# Diag64Cart.net
KiCad netlist of a schematic drawn in EAGLE
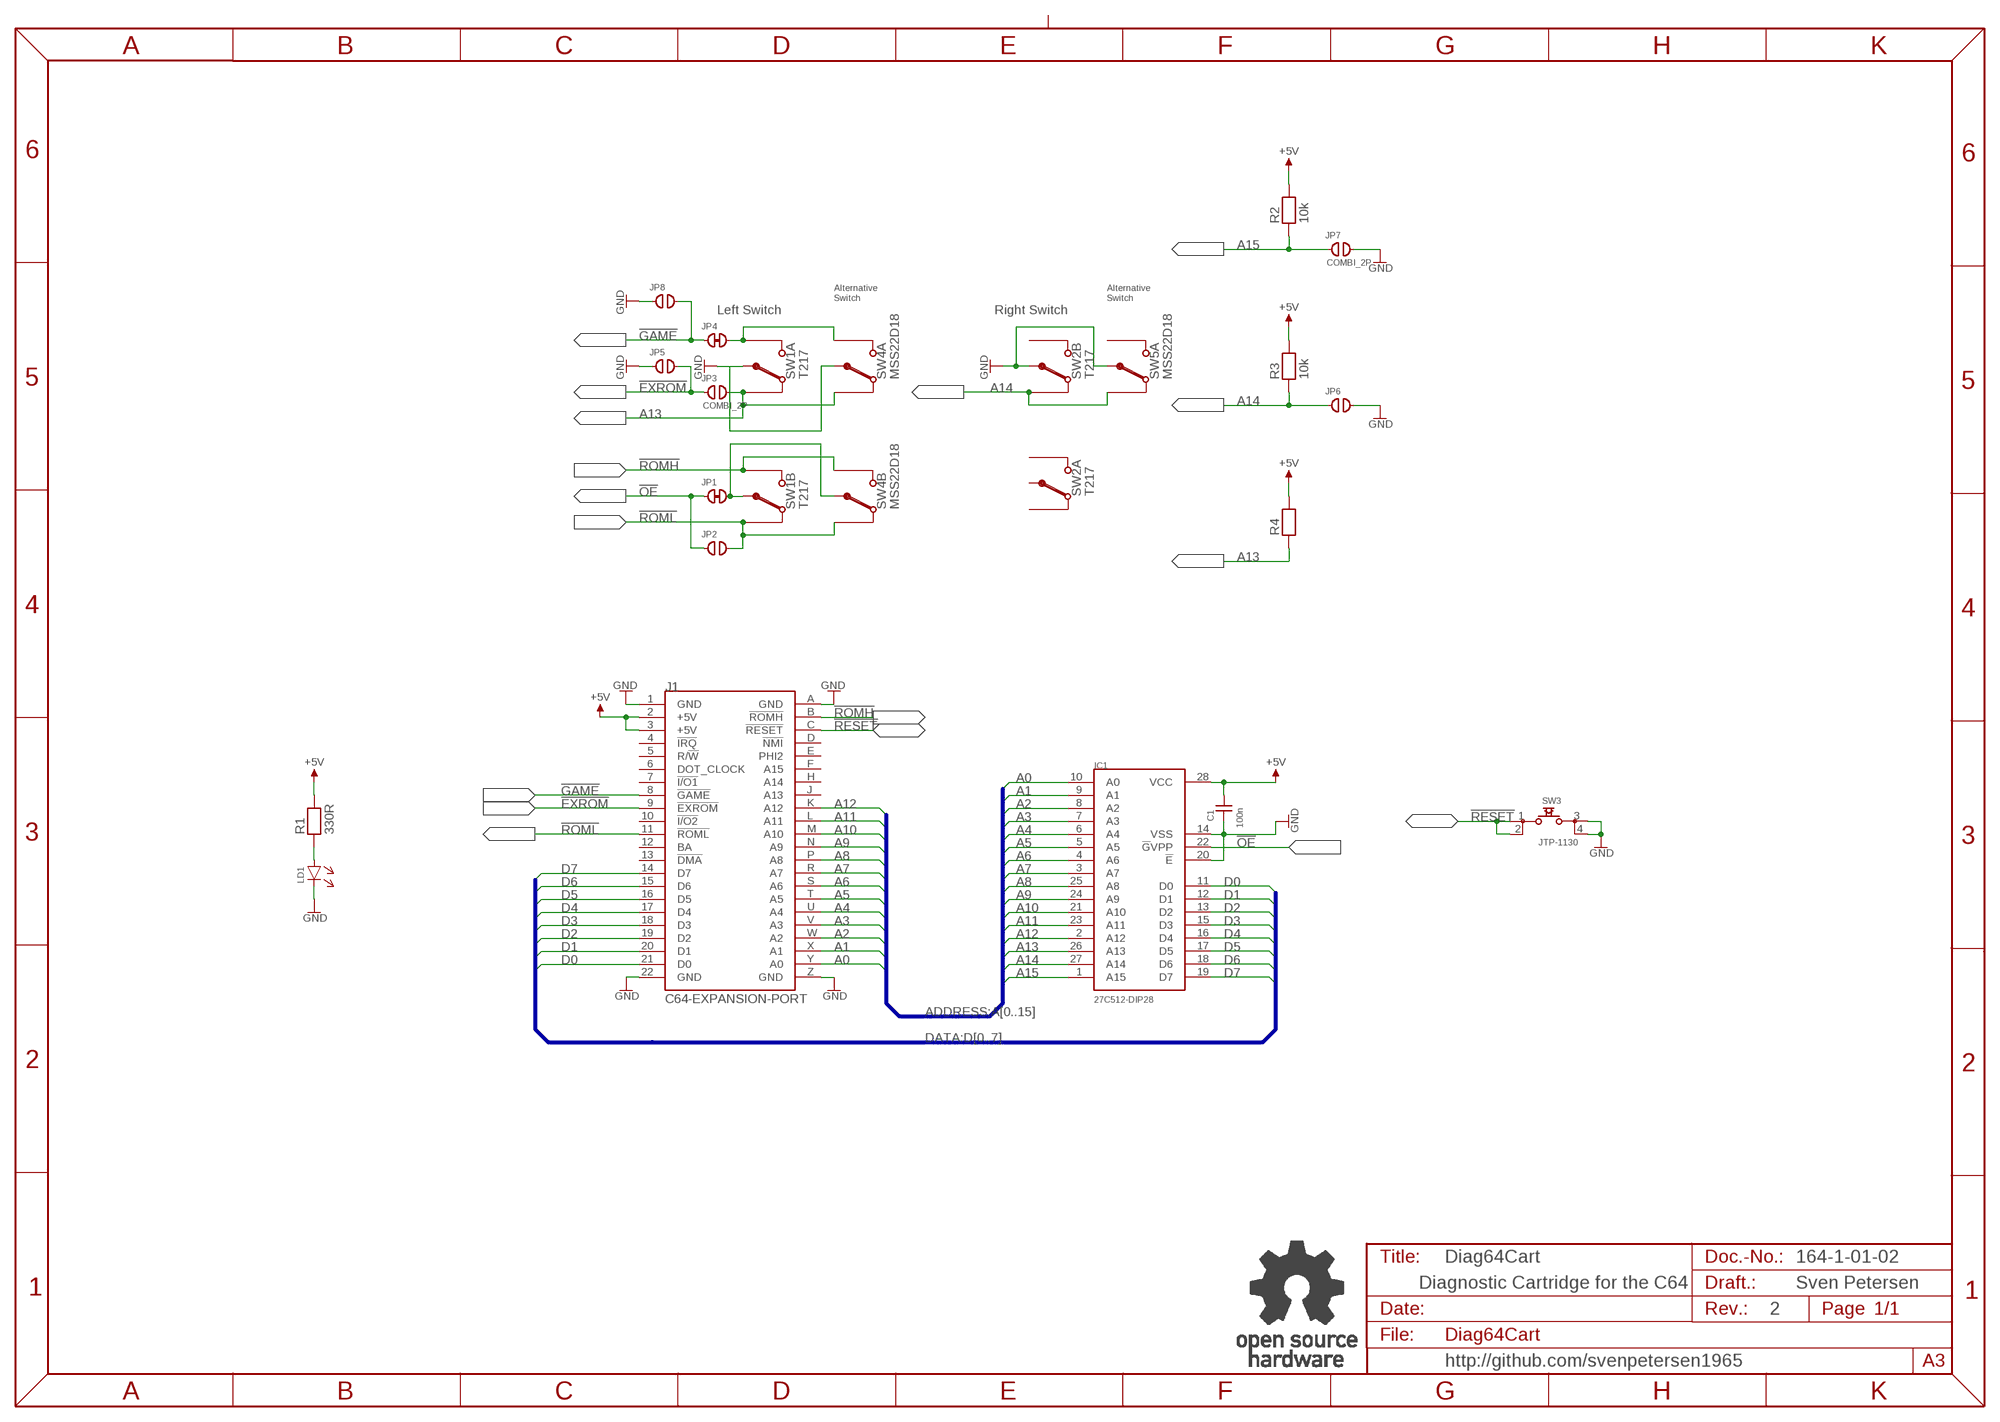
[diagram p0: schematic, sheet 1]

(export (version "E")
  (design (tool "Eeschema 10.0.6"))
  (components
    (comp (ref "C1")
      (value "100n")
      (footprint "eagle-import:C-2,5")
      (libsource (lib "eagle-import") (part "CAP01"))
    )
    (comp (ref "IC1")
      (value "27C512-DIP28")
      (footprint "eagle-import:DIL28-6")
      (libsource (lib "eagle-import") (part "M27C512-DIP28"))
    )
    (comp (ref "J1")
      (value "C64-EXPANSION-PORT")
      (footprint "eagle-import:EXPANSIO_SQ")
      (libsource (lib "eagle-import") (part "C64-EXPANSIONPNARROW"))
    )
    (comp (ref "JP1")
      (value "CLOSED")
      (footprint "eagle-import:CP_CL")
      (libsource (lib "eagle-import") (part "CLOSED"))
    )
    (comp (ref "JP2")
      (value "OPEN")
      (footprint "eagle-import:CP_OP")
      (libsource (lib "eagle-import") (part "OPEN"))
    )
    (comp (ref "JP3")
      (value "COMBI_2P")
      (footprint "eagle-import:COMBI-2P")
      (libsource (lib "eagle-import") (part "COMBI_2P"))
    )
    (comp (ref "JP4")
      (value "CLOSED")
      (footprint "eagle-import:CP_CL")
      (libsource (lib "eagle-import") (part "CLOSED"))
    )
    (comp (ref "JP5")
      (value "OPEN")
      (footprint "eagle-import:CP_OP")
      (libsource (lib "eagle-import") (part "OPEN"))
    )
    (comp (ref "JP6")
      (value "OPEN")
      (footprint "eagle-import:CP_OP")
      (libsource (lib "eagle-import") (part "OPEN"))
    )
    (comp (ref "JP7")
      (value "COMBI_2P")
      (footprint "eagle-import:COMBI-2P")
      (libsource (lib "eagle-import") (part "COMBI_2P"))
    )
    (comp (ref "JP8")
      (value "OPEN")
      (footprint "eagle-import:CP_OP")
      (libsource (lib "eagle-import") (part "OPEN"))
    )
    (comp (ref "LD1")
      (value "3MM")
      (footprint "eagle-import:3MM")
      (libsource (lib "eagle-import") (part "3MM"))
    )
    (comp (ref "R1")
      (value "330R")
      (footprint "eagle-import:R-10")
      (libsource (lib "eagle-import") (part "RES04"))
    )
    (comp (ref "R2")
      (value "10k")
      (footprint "eagle-import:R-10")
      (libsource (lib "eagle-import") (part "RES04"))
    )
    (comp (ref "R3")
      (value "10k")
      (footprint "eagle-import:R-10")
      (libsource (lib "eagle-import") (part "RES04"))
    )
    (comp (ref "R4")
      (value "10k")
      (footprint "eagle-import:R-10")
      (libsource (lib "eagle-import") (part "RES04"))
    )
    (comp (ref "SW1")
      (value "T217")
      (footprint "eagle-import:T217_SIDE")
      (libsource (lib "eagle-import") (part "T217"))
    )
    (comp (ref "SW2")
      (value "T217")
      (footprint "eagle-import:T217_SIDE")
      (libsource (lib "eagle-import") (part "T217"))
    )
    (comp (ref "SW3")
      (value "JTP-1130")
      (footprint "eagle-import:JTP-1130")
      (libsource (lib "eagle-import") (part "JTP-1130"))
    )
    (comp (ref "SW4")
      (value "MSS22D18")
      (footprint "eagle-import:DPDT_9MM")
      (libsource (lib "eagle-import") (part "DPDT_9MM"))
    )
    (comp (ref "SW5")
      (value "MSS22D18")
      (footprint "eagle-import:DPDT_9MM")
      (libsource (lib "eagle-import") (part "DPDT_9MM"))
    )
    (comp (ref "U$43")
      (value "OPEN_SOURCE_HW")
      (footprint "eagle-import:OPENHW")
      (libsource (lib "eagle-import") (part "OPEN_SOURCE_HW"))
    )
  )
  (nets
    (net (code "25") (name "+5V") (class "Default")
      (node (ref "C1") (pin "2") (pinfunction "2_2") (pintype "passive"))
      (node (ref "IC1") (pin "28") (pinfunction "VCC_28") (pintype "power_in"))
      (node (ref "J1") (pin "2") (pinfunction "+5V_2") (pintype "power_in"))
      (node (ref "J1") (pin "3") (pinfunction "+5V_3") (pintype "power_in"))
      (node (ref "R1") (pin "2") (pinfunction "2_2") (pintype "passive"))
      (node (ref "R2") (pin "2") (pinfunction "2_2") (pintype "passive"))
      (node (ref "R3") (pin "2") (pinfunction "2_2") (pintype "passive"))
      (node (ref "R4") (pin "2") (pinfunction "2_2") (pintype "passive"))
    )
    (net (code "26") (name "/A0") (class "Default")
      (node (ref "IC1") (pin "10") (pinfunction "A0_10") (pintype "input"))
      (node (ref "J1") (pin "Y") (pinfunction "A0_Y") (pintype "bidirectional"))
    )
    (net (code "27") (name "/A1") (class "Default")
      (node (ref "IC1") (pin "9") (pinfunction "A1_9") (pintype "input"))
      (node (ref "J1") (pin "X") (pinfunction "A1_X") (pintype "bidirectional"))
    )
    (net (code "28") (name "/A2") (class "Default")
      (node (ref "IC1") (pin "8") (pinfunction "A2_8") (pintype "input"))
      (node (ref "J1") (pin "W") (pinfunction "A2_W") (pintype "bidirectional"))
    )
    (net (code "29") (name "/A3") (class "Default")
      (node (ref "IC1") (pin "7") (pinfunction "A3_7") (pintype "input"))
      (node (ref "J1") (pin "V") (pinfunction "A3_V") (pintype "bidirectional"))
    )
    (net (code "30") (name "/A4") (class "Default")
      (node (ref "IC1") (pin "6") (pinfunction "A4_6") (pintype "input"))
      (node (ref "J1") (pin "U") (pinfunction "A4_U") (pintype "bidirectional"))
    )
    (net (code "31") (name "/A5") (class "Default")
      (node (ref "IC1") (pin "5") (pinfunction "A5_5") (pintype "input"))
      (node (ref "J1") (pin "T") (pinfunction "A5_T") (pintype "bidirectional"))
    )
    (net (code "32") (name "/A6") (class "Default")
      (node (ref "IC1") (pin "4") (pinfunction "A6_4") (pintype "input"))
      (node (ref "J1") (pin "S") (pinfunction "A6_S") (pintype "bidirectional"))
    )
    (net (code "33") (name "/A7") (class "Default")
      (node (ref "IC1") (pin "3") (pinfunction "A7_3") (pintype "input"))
      (node (ref "J1") (pin "R") (pinfunction "A7_R") (pintype "bidirectional"))
    )
    (net (code "34") (name "/A8") (class "Default")
      (node (ref "IC1") (pin "25") (pinfunction "A8_25") (pintype "input"))
      (node (ref "J1") (pin "P") (pinfunction "A8_P") (pintype "bidirectional"))
    )
    (net (code "35") (name "/A9") (class "Default")
      (node (ref "IC1") (pin "24") (pinfunction "A9_24") (pintype "input"))
      (node (ref "J1") (pin "N") (pinfunction "A9_N") (pintype "bidirectional"))
    )
    (net (code "36") (name "/A10") (class "Default")
      (node (ref "IC1") (pin "21") (pinfunction "A10_21") (pintype "input"))
      (node (ref "J1") (pin "M") (pinfunction "A10_M") (pintype "bidirectional"))
    )
    (net (code "37") (name "/A11") (class "Default")
      (node (ref "IC1") (pin "23") (pinfunction "A11_23") (pintype "input"))
      (node (ref "J1") (pin "L") (pinfunction "A11_L") (pintype "bidirectional"))
    )
    (net (code "38") (name "/A12") (class "Default")
      (node (ref "IC1") (pin "2") (pinfunction "A12_2") (pintype "input"))
      (node (ref "J1") (pin "K") (pinfunction "A12_K") (pintype "bidirectional"))
    )
    (net (code "39") (name "/A13") (class "Default")
      (node (ref "IC1") (pin "26") (pinfunction "A13_26") (pintype "input"))
      (node (ref "JP3") (pin "2") (pinfunction "2_2") (pintype "passive"))
      (node (ref "R4") (pin "1") (pinfunction "1_1") (pintype "passive"))
      (node (ref "SW1") (pin "DWN1") (pinfunction "DWN_DWN1") (pintype "bidirectional"))
      (node (ref "SW4") (pin "3") (pinfunction "DWN_3") (pintype "bidirectional"))
    )
    (net (code "40") (name "/A14") (class "Default")
      (node (ref "IC1") (pin "27") (pinfunction "A14_27") (pintype "input"))
      (node (ref "JP6") (pin "1") (pinfunction "1_1") (pintype "passive"))
      (node (ref "R3") (pin "1") (pinfunction "1_1") (pintype "passive"))
      (node (ref "SW2") (pin "DWN2") (pinfunction "DWN_DWN2") (pintype "bidirectional"))
      (node (ref "SW5") (pin "3") (pinfunction "DWN_3") (pintype "bidirectional"))
    )
    (net (code "41") (name "/A15") (class "Default")
      (node (ref "IC1") (pin "1") (pinfunction "A15_1") (pintype "input"))
      (node (ref "JP7") (pin "1") (pinfunction "1_1") (pintype "passive"))
      (node (ref "R2") (pin "1") (pinfunction "1_1") (pintype "passive"))
    )
    (net (code "43") (name "/D0") (class "Default")
      (node (ref "IC1") (pin "11") (pinfunction "D0_11") (pintype "bidirectional"))
      (node (ref "J1") (pin "21") (pinfunction "D0_21") (pintype "bidirectional"))
    )
    (net (code "44") (name "/D1") (class "Default")
      (node (ref "IC1") (pin "12") (pinfunction "D1_12") (pintype "bidirectional"))
      (node (ref "J1") (pin "20") (pinfunction "D1_20") (pintype "bidirectional"))
    )
    (net (code "45") (name "/D2") (class "Default")
      (node (ref "IC1") (pin "13") (pinfunction "D2_13") (pintype "bidirectional"))
      (node (ref "J1") (pin "19") (pinfunction "D2_19") (pintype "bidirectional"))
    )
    (net (code "46") (name "/D3") (class "Default")
      (node (ref "IC1") (pin "15") (pinfunction "D3_15") (pintype "bidirectional"))
      (node (ref "J1") (pin "18") (pinfunction "D3_18") (pintype "bidirectional"))
    )
    (net (code "47") (name "/D4") (class "Default")
      (node (ref "IC1") (pin "16") (pinfunction "D4_16") (pintype "bidirectional"))
      (node (ref "J1") (pin "17") (pinfunction "D4_17") (pintype "bidirectional"))
    )
    (net (code "48") (name "/D5") (class "Default")
      (node (ref "IC1") (pin "17") (pinfunction "D5_17") (pintype "bidirectional"))
      (node (ref "J1") (pin "16") (pinfunction "D5_16") (pintype "bidirectional"))
    )
    (net (code "49") (name "/D6") (class "Default")
      (node (ref "IC1") (pin "18") (pinfunction "D6_18") (pintype "bidirectional"))
      (node (ref "J1") (pin "15") (pinfunction "D6_15") (pintype "bidirectional"))
    )
    (net (code "50") (name "/D7") (class "Default")
      (node (ref "IC1") (pin "19") (pinfunction "D7_19") (pintype "bidirectional"))
      (node (ref "J1") (pin "14") (pinfunction "D7_14") (pintype "bidirectional"))
    )
    (net (code "52") (name "/~{EXROM}") (class "Default")
      (node (ref "J1") (pin "9") (pinfunction "~{EXROM}_9") (pintype "input"))
      (node (ref "JP3") (pin "1") (pinfunction "1_1") (pintype "passive"))
      (node (ref "JP5") (pin "2") (pinfunction "2_2") (pintype "passive"))
    )
    (net (code "53") (name "/~{GAME}") (class "Default")
      (node (ref "J1") (pin "8") (pinfunction "~{GAME}_8") (pintype "input"))
      (node (ref "JP4") (pin "1") (pinfunction "1_1") (pintype "passive"))
      (node (ref "JP8") (pin "2") (pinfunction "2_2") (pintype "passive"))
    )
    (net (code "54") (name "/~{OE}") (class "Default")
      (node (ref "IC1") (pin "22") (pinfunction "~{G}VPP_22") (pintype "input"))
      (node (ref "JP1") (pin "1") (pinfunction "1_1") (pintype "passive"))
      (node (ref "JP2") (pin "1") (pinfunction "1_1") (pintype "passive"))
    )
    (net (code "55") (name "/~{RESET}") (class "Default")
      (node (ref "J1") (pin "C") (pinfunction "~{RESET}_C") (pintype "open_collector"))
      (node (ref "SW3") (pin "1") (pinfunction "1_1") (pintype "passive"))
      (node (ref "SW3") (pin "2") (pinfunction "2_2") (pintype "passive"))
    )
    (net (code "56") (name "/~{ROMH}") (class "Default")
      (node (ref "J1") (pin "B") (pinfunction "~{ROMH}_B") (pintype "output"))
      (node (ref "SW1") (pin "UP2") (pinfunction "UP_UP2") (pintype "bidirectional"))
      (node (ref "SW4") (pin "6") (pinfunction "UP_6") (pintype "bidirectional"))
    )
    (net (code "57") (name "/~{ROML}") (class "Default")
      (node (ref "J1") (pin "11") (pinfunction "~{ROML}_11") (pintype "output"))
      (node (ref "JP2") (pin "2") (pinfunction "2_2") (pintype "passive"))
      (node (ref "SW1") (pin "DWN2") (pinfunction "DWN_DWN2") (pintype "bidirectional"))
      (node (ref "SW4") (pin "4") (pinfunction "DWN_4") (pintype "bidirectional"))
    )
    (net (code "58") (name "GND") (class "Default")
      (node (ref "C1") (pin "1") (pinfunction "1_1") (pintype "passive"))
      (node (ref "IC1") (pin "14") (pinfunction "VSS_14") (pintype "power_in"))
      (node (ref "IC1") (pin "20") (pinfunction "~{E}_20") (pintype "input"))
      (node (ref "J1") (pin "1") (pinfunction "GND_1") (pintype "power_in"))
      (node (ref "J1") (pin "22") (pinfunction "GND_22") (pintype "power_in"))
      (node (ref "J1") (pin "A") (pinfunction "GND_A") (pintype "power_in"))
      (node (ref "J1") (pin "Z") (pinfunction "GND_Z") (pintype "power_in"))
      (node (ref "JP5") (pin "1") (pinfunction "1_1") (pintype "passive"))
      (node (ref "JP6") (pin "2") (pinfunction "2_2") (pintype "passive"))
      (node (ref "JP7") (pin "2") (pinfunction "2_2") (pintype "passive"))
      (node (ref "JP8") (pin "1") (pinfunction "1_1") (pintype "passive"))
      (node (ref "LD1") (pin "C") (pinfunction "K_C") (pintype "bidirectional"))
      (node (ref "SW1") (pin "COM1") (pinfunction "COM_COM1") (pintype "bidirectional"))
      (node (ref "SW2") (pin "COM2") (pinfunction "COM_COM2") (pintype "bidirectional"))
      (node (ref "SW3") (pin "3") (pinfunction "3_3") (pintype "passive"))
      (node (ref "SW3") (pin "4") (pinfunction "4_4") (pintype "passive"))
      (node (ref "SW5") (pin "2") (pinfunction "COM_2") (pintype "bidirectional"))
    )
    (net (code "59") (name "Net-(LD1-PadA)") (class "Default")
      (node (ref "LD1") (pin "A") (pinfunction "A_A") (pintype "bidirectional"))
      (node (ref "R1") (pin "1") (pinfunction "1_1") (pintype "passive"))
    )
    (net (code "60") (name "Net-(SW1A-UP)") (class "Default")
      (node (ref "JP4") (pin "2") (pinfunction "2_2") (pintype "passive"))
      (node (ref "SW1") (pin "UP1") (pinfunction "UP_UP1") (pintype "bidirectional"))
      (node (ref "SW4") (pin "1") (pinfunction "UP_1") (pintype "bidirectional"))
    )
    (net (code "61") (name "Net-(SW1B-COM)") (class "Default")
      (node (ref "JP1") (pin "2") (pinfunction "2_2") (pintype "passive"))
      (node (ref "SW1") (pin "COM2") (pinfunction "COM_COM2") (pintype "bidirectional"))
      (node (ref "SW4") (pin "5") (pinfunction "COM_5") (pintype "bidirectional"))
    )
    (net (code "62") (name "unconnected-(J1-A13-PadJ)") (class "Default")
      (node (ref "J1") (pin "J") (pinfunction "A13_J") (pintype "bidirectional"))
    )
    (net (code "63") (name "unconnected-(J1-A14-PadH)") (class "Default")
      (node (ref "J1") (pin "H") (pinfunction "A14_H") (pintype "bidirectional"))
    )
    (net (code "64") (name "unconnected-(J1-A15-PadF)") (class "Default")
      (node (ref "J1") (pin "F") (pinfunction "A15_F") (pintype "bidirectional"))
    )
    (net (code "65") (name "unconnected-(J1-BA-Pad12)") (class "Default")
      (node (ref "J1") (pin "12") (pinfunction "BA_12") (pintype "output"))
    )
    (net (code "66") (name "unconnected-(J1-DOT_CLOCK-Pad6)") (class "Default")
      (node (ref "J1") (pin "6") (pinfunction "DOT_CLOCK_6") (pintype "output"))
    )
    (net (code "67") (name "unconnected-(J1-PHI2-PadE)") (class "Default")
      (node (ref "J1") (pin "E") (pinfunction "PHI2_E") (pintype "output"))
    )
    (net (code "68") (name "unconnected-(J1-R{slash}~{W}-Pad5)") (class "Default")
      (node (ref "J1") (pin "5") (pinfunction "R/~{W}_5") (pintype "output"))
    )
    (net (code "69") (name "unconnected-(J1-~{DMA}-Pad13)") (class "Default")
      (node (ref "J1") (pin "13") (pinfunction "~{DMA}_13") (pintype "input"))
    )
    (net (code "70") (name "unconnected-(J1-~{IRQ}-Pad4)") (class "Default")
      (node (ref "J1") (pin "4") (pinfunction "~{IRQ}_4") (pintype "input"))
    )
    (net (code "71") (name "unconnected-(J1-~{I{slash}O1}-Pad7)") (class "Default")
      (node (ref "J1") (pin "7") (pinfunction "~{I/O1}_7") (pintype "output"))
    )
    (net (code "72") (name "unconnected-(J1-~{I{slash}O2}-Pad10)") (class "Default")
      (node (ref "J1") (pin "10") (pinfunction "~{I/O2}_10") (pintype "output"))
    )
    (net (code "73") (name "unconnected-(J1-~{NMI}-PadD)") (class "Default")
      (node (ref "J1") (pin "D") (pinfunction "~{NMI}_D") (pintype "input"))
    )
    (net (code "74") (name "unconnected-(SW2A-COM-PadCOM1)") (class "Default")
      (node (ref "SW2") (pin "COM1") (pinfunction "COM_COM1") (pintype "bidirectional"))
    )
    (net (code "75") (name "unconnected-(SW2A-DWN-PadDWN1)") (class "Default")
      (node (ref "SW2") (pin "DWN1") (pinfunction "DWN_DWN1") (pintype "bidirectional"))
    )
    (net (code "76") (name "unconnected-(SW2A-UP-PadUP1)") (class "Default")
      (node (ref "SW2") (pin "UP1") (pinfunction "UP_UP1") (pintype "bidirectional"))
    )
    (net (code "77") (name "unconnected-(SW2B-UP-PadUP2)") (class "Default")
      (node (ref "SW2") (pin "UP2") (pinfunction "UP_UP2") (pintype "bidirectional"))
    )
    (net (code "78") (name "unconnected-(SW4A-COM-Pad2)") (class "Default")
      (node (ref "SW4") (pin "2") (pinfunction "COM_2") (pintype "bidirectional"))
    )
    (net (code "79") (name "unconnected-(SW5A-UP-Pad1)") (class "Default")
      (node (ref "SW5") (pin "1") (pinfunction "UP_1") (pintype "bidirectional"))
    )
  )
)
